# R181C.net
KiCad netlist of a schematic drawn in EAGLE
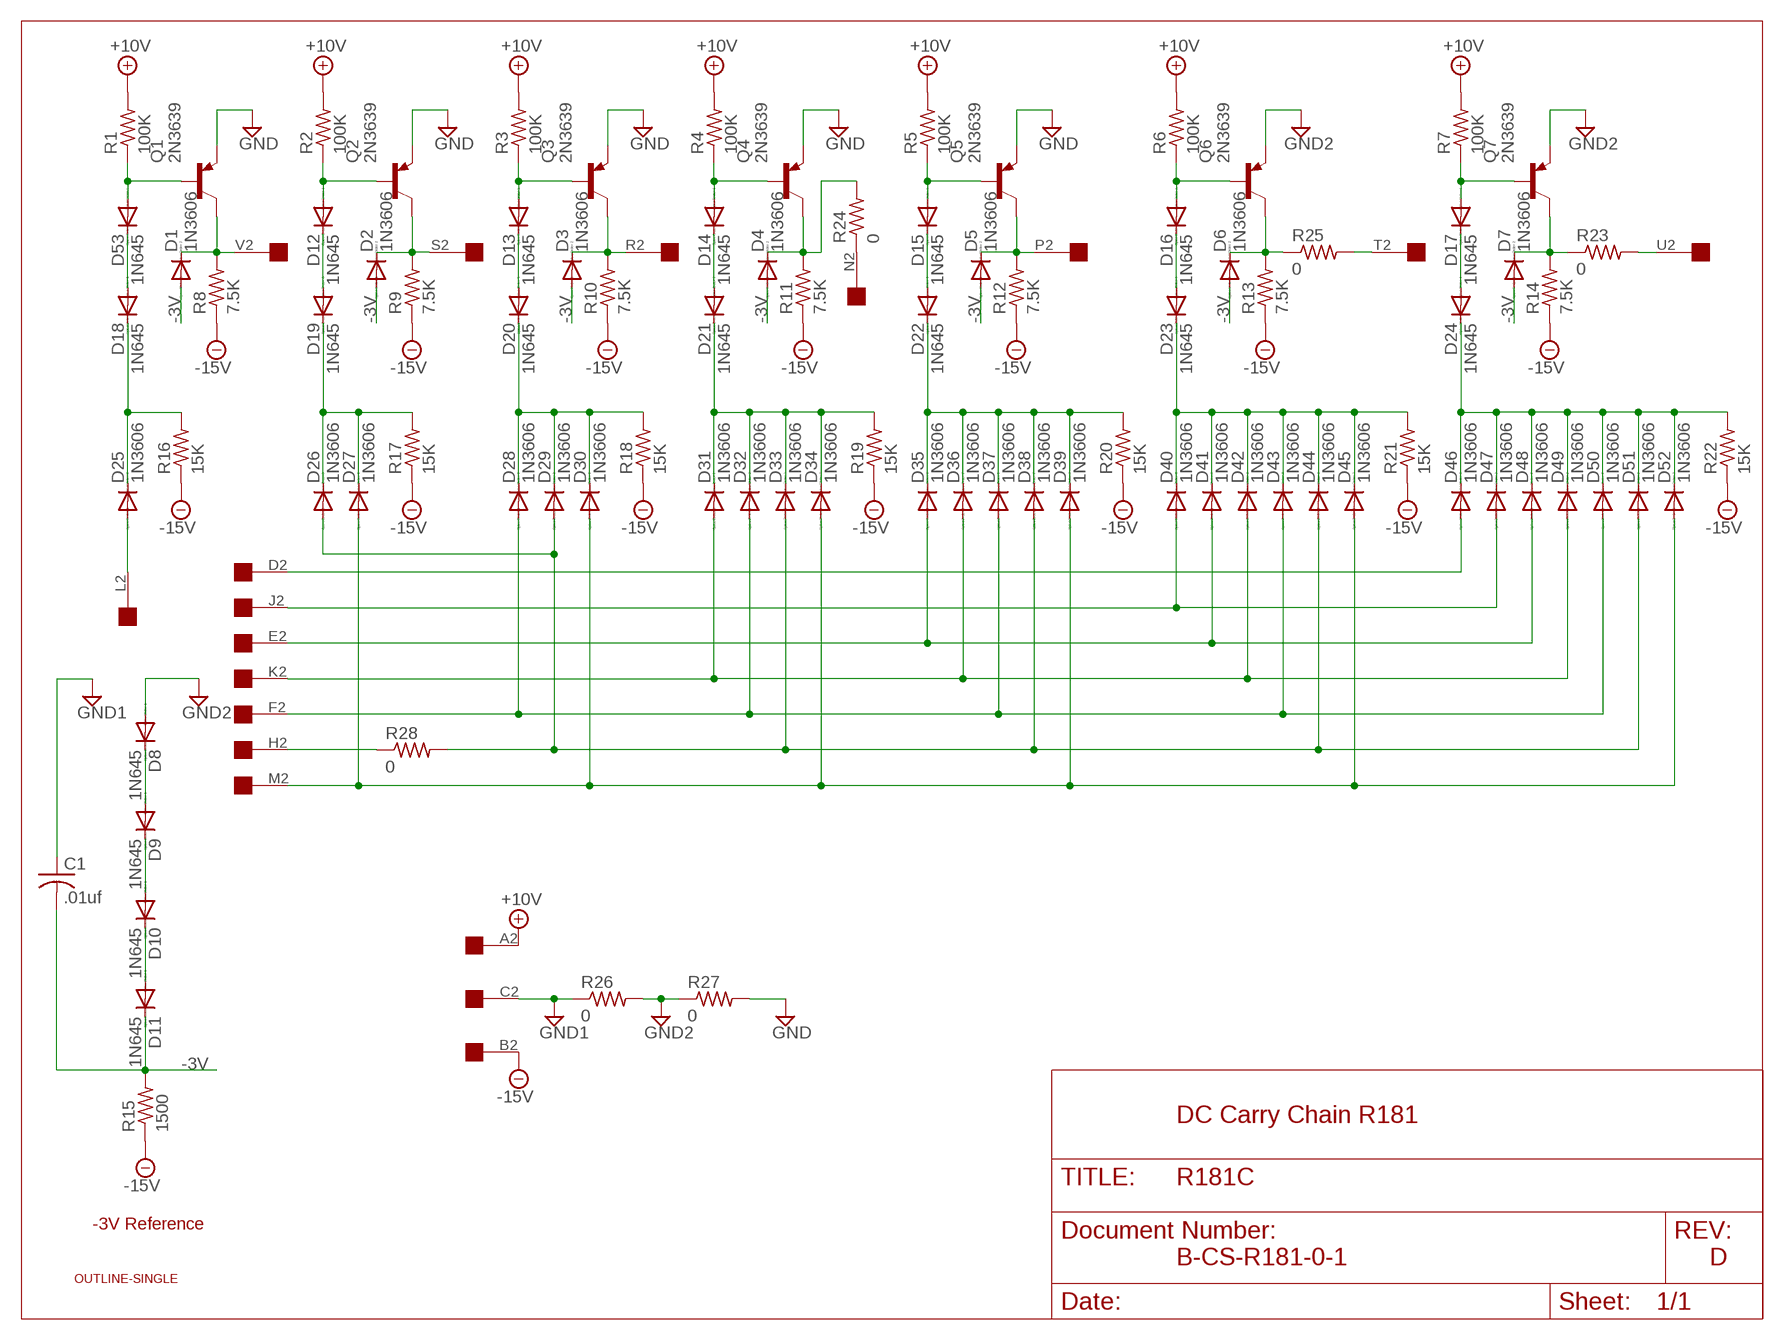
[diagram p0: schematic, sheet 1]

(export (version "E")
  (design (tool "Eeschema 10.0.6"))
  (components
    (comp (ref "C1")
      (value ".01uf")
      (footprint "eagle-import:C050-025X075")
      (libsource (lib "eagle-import") (part "C-US050-025X075"))
    )
    (comp (ref "D1")
      (value "1N3606")
      (footprint "eagle-import:DO35-10")
      (libsource (lib "eagle-import") (part "1N4148DO35-10"))
    )
    (comp (ref "D2")
      (value "1N3606")
      (footprint "eagle-import:DO35-10")
      (libsource (lib "eagle-import") (part "1N4148DO35-10"))
    )
    (comp (ref "D3")
      (value "1N3606")
      (footprint "eagle-import:DO35-10")
      (libsource (lib "eagle-import") (part "1N4148DO35-10"))
    )
    (comp (ref "D4")
      (value "1N3606")
      (footprint "eagle-import:DO35-10")
      (libsource (lib "eagle-import") (part "1N4148DO35-10"))
    )
    (comp (ref "D5")
      (value "1N3606")
      (footprint "eagle-import:DO35-10")
      (libsource (lib "eagle-import") (part "1N4148DO35-10"))
    )
    (comp (ref "D6")
      (value "1N3606")
      (footprint "eagle-import:DO35-10")
      (libsource (lib "eagle-import") (part "1N4148DO35-10"))
    )
    (comp (ref "D7")
      (value "1N3606")
      (footprint "eagle-import:DO35-10")
      (libsource (lib "eagle-import") (part "1N4148DO35-10"))
    )
    (comp (ref "D8")
      (value "1N645")
      (footprint "eagle-import:DO35-10")
      (libsource (lib "eagle-import") (part "1N4148DO35-10"))
    )
    (comp (ref "D9")
      (value "1N645")
      (footprint "eagle-import:DO35-10")
      (libsource (lib "eagle-import") (part "1N4148DO35-10"))
    )
    (comp (ref "D10")
      (value "1N645")
      (footprint "eagle-import:DO35-10")
      (libsource (lib "eagle-import") (part "1N4148DO35-10"))
    )
    (comp (ref "D11")
      (value "1N645")
      (footprint "eagle-import:DO35-10")
      (libsource (lib "eagle-import") (part "1N4148DO35-10"))
    )
    (comp (ref "D12")
      (value "1N645")
      (footprint "eagle-import:DO35-10")
      (libsource (lib "eagle-import") (part "1N4148DO35-10"))
    )
    (comp (ref "D13")
      (value "1N645")
      (footprint "eagle-import:DO35-10")
      (libsource (lib "eagle-import") (part "1N4148DO35-10"))
    )
    (comp (ref "D14")
      (value "1N645")
      (footprint "eagle-import:DO35-10")
      (libsource (lib "eagle-import") (part "1N4148DO35-10"))
    )
    (comp (ref "D15")
      (value "1N645")
      (footprint "eagle-import:DO35-10")
      (libsource (lib "eagle-import") (part "1N4148DO35-10"))
    )
    (comp (ref "D16")
      (value "1N645")
      (footprint "eagle-import:DO35-10")
      (libsource (lib "eagle-import") (part "1N4148DO35-10"))
    )
    (comp (ref "D17")
      (value "1N645")
      (footprint "eagle-import:DO35-10")
      (libsource (lib "eagle-import") (part "1N4148DO35-10"))
    )
    (comp (ref "D18")
      (value "1N645")
      (footprint "eagle-import:DO35-10")
      (libsource (lib "eagle-import") (part "1N4148DO35-10"))
    )
    (comp (ref "D19")
      (value "1N645")
      (footprint "eagle-import:DO35-10")
      (libsource (lib "eagle-import") (part "1N4148DO35-10"))
    )
    (comp (ref "D20")
      (value "1N645")
      (footprint "eagle-import:DO35-10")
      (libsource (lib "eagle-import") (part "1N4148DO35-10"))
    )
    (comp (ref "D21")
      (value "1N645")
      (footprint "eagle-import:DO35-10")
      (libsource (lib "eagle-import") (part "1N4148DO35-10"))
    )
    (comp (ref "D22")
      (value "1N645")
      (footprint "eagle-import:DO35-10")
      (libsource (lib "eagle-import") (part "1N4148DO35-10"))
    )
    (comp (ref "D23")
      (value "1N645")
      (footprint "eagle-import:DO35-10")
      (libsource (lib "eagle-import") (part "1N4148DO35-10"))
    )
    (comp (ref "D24")
      (value "1N645")
      (footprint "eagle-import:DO35-10")
      (libsource (lib "eagle-import") (part "1N4148DO35-10"))
    )
    (comp (ref "D25")
      (value "1N3606")
      (footprint "eagle-import:DO35-10")
      (libsource (lib "eagle-import") (part "1N4148DO35-10"))
    )
    (comp (ref "D26")
      (value "1N3606")
      (footprint "eagle-import:DO35-10")
      (libsource (lib "eagle-import") (part "1N4148DO35-10"))
    )
    (comp (ref "D27")
      (value "1N3606")
      (footprint "eagle-import:DO35-10")
      (libsource (lib "eagle-import") (part "1N4148DO35-10"))
    )
    (comp (ref "D28")
      (value "1N3606")
      (footprint "eagle-import:DO35-10")
      (libsource (lib "eagle-import") (part "1N4148DO35-10"))
    )
    (comp (ref "D29")
      (value "1N3606")
      (footprint "eagle-import:DO35-10")
      (libsource (lib "eagle-import") (part "1N4148DO35-10"))
    )
    (comp (ref "D30")
      (value "1N3606")
      (footprint "eagle-import:DO35-10")
      (libsource (lib "eagle-import") (part "1N4148DO35-10"))
    )
    (comp (ref "D31")
      (value "1N3606")
      (footprint "eagle-import:DO35-10")
      (libsource (lib "eagle-import") (part "1N4148DO35-10"))
    )
    (comp (ref "D32")
      (value "1N3606")
      (footprint "eagle-import:DO35-10")
      (libsource (lib "eagle-import") (part "1N4148DO35-10"))
    )
    (comp (ref "D33")
      (value "1N3606")
      (footprint "eagle-import:DO35-10")
      (libsource (lib "eagle-import") (part "1N4148DO35-10"))
    )
    (comp (ref "D34")
      (value "1N3606")
      (footprint "eagle-import:DO35-10")
      (libsource (lib "eagle-import") (part "1N4148DO35-10"))
    )
    (comp (ref "D35")
      (value "1N3606")
      (footprint "eagle-import:DO35-10")
      (libsource (lib "eagle-import") (part "1N4148DO35-10"))
    )
    (comp (ref "D36")
      (value "1N3606")
      (footprint "eagle-import:DO35-10")
      (libsource (lib "eagle-import") (part "1N4148DO35-10"))
    )
    (comp (ref "D37")
      (value "1N3606")
      (footprint "eagle-import:DO35-10")
      (libsource (lib "eagle-import") (part "1N4148DO35-10"))
    )
    (comp (ref "D38")
      (value "1N3606")
      (footprint "eagle-import:DO35-10")
      (libsource (lib "eagle-import") (part "1N4148DO35-10"))
    )
    (comp (ref "D39")
      (value "1N3606")
      (footprint "eagle-import:DO35-10")
      (libsource (lib "eagle-import") (part "1N4148DO35-10"))
    )
    (comp (ref "D40")
      (value "1N3606")
      (footprint "eagle-import:DO35-10")
      (libsource (lib "eagle-import") (part "1N4148DO35-10"))
    )
    (comp (ref "D41")
      (value "1N3606")
      (footprint "eagle-import:DO35-10")
      (libsource (lib "eagle-import") (part "1N4148DO35-10"))
    )
    (comp (ref "D42")
      (value "1N3606")
      (footprint "eagle-import:DO35-10")
      (libsource (lib "eagle-import") (part "1N4148DO35-10"))
    )
    (comp (ref "D43")
      (value "1N3606")
      (footprint "eagle-import:DO35-10")
      (libsource (lib "eagle-import") (part "1N4148DO35-10"))
    )
    (comp (ref "D44")
      (value "1N3606")
      (footprint "eagle-import:DO35-10")
      (libsource (lib "eagle-import") (part "1N4148DO35-10"))
    )
    (comp (ref "D45")
      (value "1N3606")
      (footprint "eagle-import:DO35-10")
      (libsource (lib "eagle-import") (part "1N4148DO35-10"))
    )
    (comp (ref "D46")
      (value "1N3606")
      (footprint "eagle-import:DO35-10")
      (libsource (lib "eagle-import") (part "1N4148DO35-10"))
    )
    (comp (ref "D47")
      (value "1N3606")
      (footprint "eagle-import:DO35-10")
      (libsource (lib "eagle-import") (part "1N4148DO35-10"))
    )
    (comp (ref "D48")
      (value "1N3606")
      (footprint "eagle-import:DO35-10")
      (libsource (lib "eagle-import") (part "1N4148DO35-10"))
    )
    (comp (ref "D49")
      (value "1N3606")
      (footprint "eagle-import:DO35-10")
      (libsource (lib "eagle-import") (part "1N4148DO35-10"))
    )
    (comp (ref "D50")
      (value "1N3606")
      (footprint "eagle-import:DO35-10")
      (libsource (lib "eagle-import") (part "1N4148DO35-10"))
    )
    (comp (ref "D51")
      (value "1N3606")
      (footprint "eagle-import:DO35-10")
      (libsource (lib "eagle-import") (part "1N4148DO35-10"))
    )
    (comp (ref "D52")
      (value "1N3606")
      (footprint "eagle-import:DO35-10")
      (libsource (lib "eagle-import") (part "1N4148DO35-10"))
    )
    (comp (ref "D53")
      (value "1N645")
      (footprint "eagle-import:DO35-10")
      (libsource (lib "eagle-import") (part "1N4148DO35-10"))
    )
    (comp (ref "Q1")
      (value "2N3639")
      (footprint "eagle-import:TO39")
      (libsource (lib "eagle-import") (part "2N3637"))
    )
    (comp (ref "Q2")
      (value "2N3639")
      (footprint "eagle-import:TO39")
      (libsource (lib "eagle-import") (part "2N3637"))
    )
    (comp (ref "Q3")
      (value "2N3639")
      (footprint "eagle-import:TO39")
      (libsource (lib "eagle-import") (part "2N3637"))
    )
    (comp (ref "Q4")
      (value "2N3639")
      (footprint "eagle-import:TO39")
      (libsource (lib "eagle-import") (part "2N3637"))
    )
    (comp (ref "Q5")
      (value "2N3639")
      (footprint "eagle-import:TO39")
      (libsource (lib "eagle-import") (part "2N3637"))
    )
    (comp (ref "Q6")
      (value "2N3639")
      (footprint "eagle-import:TO39")
      (libsource (lib "eagle-import") (part "2N3637"))
    )
    (comp (ref "Q7")
      (value "2N3639")
      (footprint "eagle-import:TO39")
      (libsource (lib "eagle-import") (part "2N3637"))
    )
    (comp (ref "R1")
      (value "100K")
      (footprint "eagle-import:0207_10")
      (libsource (lib "eagle-import") (part "R-US_0207/10"))
    )
    (comp (ref "R2")
      (value "100K")
      (footprint "eagle-import:0207_10")
      (libsource (lib "eagle-import") (part "R-US_0207/10"))
    )
    (comp (ref "R3")
      (value "100K")
      (footprint "eagle-import:0207_10")
      (libsource (lib "eagle-import") (part "R-US_0207/10"))
    )
    (comp (ref "R4")
      (value "100K")
      (footprint "eagle-import:0207_10")
      (libsource (lib "eagle-import") (part "R-US_0207/10"))
    )
    (comp (ref "R5")
      (value "100K")
      (footprint "eagle-import:0207_10")
      (libsource (lib "eagle-import") (part "R-US_0207/10"))
    )
    (comp (ref "R6")
      (value "100K")
      (footprint "eagle-import:0207_10")
      (libsource (lib "eagle-import") (part "R-US_0207/10"))
    )
    (comp (ref "R7")
      (value "100K")
      (footprint "eagle-import:0207_10")
      (libsource (lib "eagle-import") (part "R-US_0207/10"))
    )
    (comp (ref "R8")
      (value "7.5K")
      (footprint "eagle-import:0207_10")
      (libsource (lib "eagle-import") (part "R-US_0207/10"))
    )
    (comp (ref "R9")
      (value "7.5K")
      (footprint "eagle-import:0207_10")
      (libsource (lib "eagle-import") (part "R-US_0207/10"))
    )
    (comp (ref "R10")
      (value "7.5K")
      (footprint "eagle-import:0207_10")
      (libsource (lib "eagle-import") (part "R-US_0207/10"))
    )
    (comp (ref "R11")
      (value "7.5K")
      (footprint "eagle-import:0207_10")
      (libsource (lib "eagle-import") (part "R-US_0207/10"))
    )
    (comp (ref "R12")
      (value "7.5K")
      (footprint "eagle-import:0207_10")
      (libsource (lib "eagle-import") (part "R-US_0207/10"))
    )
    (comp (ref "R13")
      (value "7.5K")
      (footprint "eagle-import:0207_10")
      (libsource (lib "eagle-import") (part "R-US_0207/10"))
    )
    (comp (ref "R14")
      (value "7.5K")
      (footprint "eagle-import:0207_10")
      (libsource (lib "eagle-import") (part "R-US_0207/10"))
    )
    (comp (ref "R15")
      (value "1500")
      (footprint "eagle-import:0207_10")
      (libsource (lib "eagle-import") (part "R-US_0207/10"))
    )
    (comp (ref "R16")
      (value "15K")
      (footprint "eagle-import:0207_10")
      (libsource (lib "eagle-import") (part "R-US_0207/10"))
    )
    (comp (ref "R17")
      (value "15K")
      (footprint "eagle-import:0207_10")
      (libsource (lib "eagle-import") (part "R-US_0207/10"))
    )
    (comp (ref "R18")
      (value "15K")
      (footprint "eagle-import:0207_10")
      (libsource (lib "eagle-import") (part "R-US_0207/10"))
    )
    (comp (ref "R19")
      (value "15K")
      (footprint "eagle-import:0207_10")
      (libsource (lib "eagle-import") (part "R-US_0207/10"))
    )
    (comp (ref "R20")
      (value "15K")
      (footprint "eagle-import:0207_10")
      (libsource (lib "eagle-import") (part "R-US_0207/10"))
    )
    (comp (ref "R21")
      (value "15K")
      (footprint "eagle-import:0207_10")
      (libsource (lib "eagle-import") (part "R-US_0207/10"))
    )
    (comp (ref "R22")
      (value "15K")
      (footprint "eagle-import:0207_10")
      (libsource (lib "eagle-import") (part "R-US_0207/10"))
    )
    (comp (ref "R23")
      (value "0")
      (footprint "eagle-import:0207_10")
      (libsource (lib "eagle-import") (part "R-US_0207/10"))
    )
    (comp (ref "R24")
      (value "0")
      (footprint "eagle-import:0207_10")
      (libsource (lib "eagle-import") (part "R-US_0207/10"))
    )
    (comp (ref "R25")
      (value "0")
      (footprint "eagle-import:0207_10")
      (libsource (lib "eagle-import") (part "R-US_0207/10"))
    )
    (comp (ref "R26")
      (value "0")
      (footprint "eagle-import:0207_10")
      (libsource (lib "eagle-import") (part "R-US_0207/10"))
    )
    (comp (ref "R27")
      (value "0")
      (footprint "eagle-import:0207_10")
      (libsource (lib "eagle-import") (part "R-US_0207/10"))
    )
    (comp (ref "R28")
      (value "0")
      (footprint "eagle-import:0207_10")
      (libsource (lib "eagle-import") (part "R-US_0207/10"))
    )
    (comp (ref "U$1")
      (value "OUTLINE-SINGLE")
      (footprint "eagle-import:SINGLE")
      (libsource (lib "eagle-import") (part "OUTLINE-SINGLE"))
    )
    (comp (ref "U$2")
      (value "EDGE-1")
      (footprint "eagle-import:EDGE-CON1")
      (libsource (lib "eagle-import") (part "EDGE-1"))
    )
  )
  (nets
    (net (code "1") (name "+10V") (class "Default")
      (node (ref "R1") (pin "2") (pinfunction "2_2") (pintype "passive"))
      (node (ref "R2") (pin "2") (pinfunction "2_2") (pintype "passive"))
      (node (ref "R3") (pin "2") (pinfunction "2_2") (pintype "passive"))
      (node (ref "R4") (pin "2") (pinfunction "2_2") (pintype "passive"))
      (node (ref "R5") (pin "2") (pinfunction "2_2") (pintype "passive"))
      (node (ref "R6") (pin "2") (pinfunction "2_2") (pintype "passive"))
      (node (ref "R7") (pin "2") (pinfunction "2_2") (pintype "passive"))
      (node (ref "U$2") (pin "A2") (pinfunction "1_A2") (pintype "bidirectional"))
    )
    (net (code "2") (name "-15V") (class "Default")
      (node (ref "R10") (pin "1") (pinfunction "1_1") (pintype "passive"))
      (node (ref "R11") (pin "1") (pinfunction "1_1") (pintype "passive"))
      (node (ref "R12") (pin "1") (pinfunction "1_1") (pintype "passive"))
      (node (ref "R13") (pin "1") (pinfunction "1_1") (pintype "passive"))
      (node (ref "R14") (pin "1") (pinfunction "1_1") (pintype "passive"))
      (node (ref "R15") (pin "1") (pinfunction "1_1") (pintype "passive"))
      (node (ref "R16") (pin "1") (pinfunction "1_1") (pintype "passive"))
      (node (ref "R17") (pin "1") (pinfunction "1_1") (pintype "passive"))
      (node (ref "R18") (pin "1") (pinfunction "1_1") (pintype "passive"))
      (node (ref "R19") (pin "1") (pinfunction "1_1") (pintype "passive"))
      (node (ref "R20") (pin "1") (pinfunction "1_1") (pintype "passive"))
      (node (ref "R21") (pin "1") (pinfunction "1_1") (pintype "passive"))
      (node (ref "R22") (pin "1") (pinfunction "1_1") (pintype "passive"))
      (node (ref "R8") (pin "1") (pinfunction "1_1") (pintype "passive"))
      (node (ref "R9") (pin "1") (pinfunction "1_1") (pintype "passive"))
      (node (ref "U$2") (pin "B2") (pinfunction "1_B2") (pintype "bidirectional"))
    )
    (net (code "3") (name "/-3V") (class "Default")
      (node (ref "C1") (pin "2") (pinfunction "2_2") (pintype "passive"))
      (node (ref "D1") (pin "A") (pinfunction "A_A") (pintype "passive"))
      (node (ref "D11") (pin "C") (pinfunction "C_C") (pintype "passive"))
      (node (ref "D2") (pin "A") (pinfunction "A_A") (pintype "passive"))
      (node (ref "D3") (pin "A") (pinfunction "A_A") (pintype "passive"))
      (node (ref "D4") (pin "A") (pinfunction "A_A") (pintype "passive"))
      (node (ref "D5") (pin "A") (pinfunction "A_A") (pintype "passive"))
      (node (ref "D6") (pin "A") (pinfunction "A_A") (pintype "passive"))
      (node (ref "D7") (pin "A") (pinfunction "A_A") (pintype "passive"))
      (node (ref "R15") (pin "2") (pinfunction "2_2") (pintype "passive"))
    )
    (net (code "4") (name "GND") (class "Default")
      (node (ref "Q1") (pin "1") (pinfunction "E_1") (pintype "passive"))
      (node (ref "Q2") (pin "1") (pinfunction "E_1") (pintype "passive"))
      (node (ref "Q3") (pin "1") (pinfunction "E_1") (pintype "passive"))
      (node (ref "Q4") (pin "1") (pinfunction "E_1") (pintype "passive"))
      (node (ref "Q5") (pin "1") (pinfunction "E_1") (pintype "passive"))
      (node (ref "R27") (pin "2") (pinfunction "2_2") (pintype "passive"))
    )
    (net (code "5") (name "GND1") (class "Default")
      (node (ref "C1") (pin "1") (pinfunction "1_1") (pintype "passive"))
      (node (ref "R26") (pin "1") (pinfunction "1_1") (pintype "passive"))
      (node (ref "U$2") (pin "C2") (pinfunction "1_C2") (pintype "bidirectional"))
    )
    (net (code "6") (name "GND2") (class "Default")
      (node (ref "D8") (pin "A") (pinfunction "A_A") (pintype "passive"))
      (node (ref "Q6") (pin "1") (pinfunction "E_1") (pintype "passive"))
      (node (ref "Q7") (pin "1") (pinfunction "E_1") (pintype "passive"))
      (node (ref "R26") (pin "2") (pinfunction "2_2") (pintype "passive"))
      (node (ref "R27") (pin "1") (pinfunction "1_1") (pintype "passive"))
    )
    (net (code "7") (name "Net-(D8-PadC)") (class "Default")
      (node (ref "D8") (pin "C") (pinfunction "C_C") (pintype "passive"))
      (node (ref "D9") (pin "A") (pinfunction "A_A") (pintype "passive"))
    )
    (net (code "8") (name "Net-(D10-PadA)") (class "Default")
      (node (ref "D10") (pin "A") (pinfunction "A_A") (pintype "passive"))
      (node (ref "D9") (pin "C") (pinfunction "C_C") (pintype "passive"))
    )
    (net (code "9") (name "Net-(D10-PadC)") (class "Default")
      (node (ref "D10") (pin "C") (pinfunction "C_C") (pintype "passive"))
      (node (ref "D11") (pin "A") (pinfunction "A_A") (pintype "passive"))
    )
    (net (code "10") (name "Net-(D12-PadC)") (class "Default")
      (node (ref "D12") (pin "C") (pinfunction "C_C") (pintype "passive"))
      (node (ref "D19") (pin "A") (pinfunction "A_A") (pintype "passive"))
    )
    (net (code "11") (name "Net-(D13-PadC)") (class "Default")
      (node (ref "D13") (pin "C") (pinfunction "C_C") (pintype "passive"))
      (node (ref "D20") (pin "A") (pinfunction "A_A") (pintype "passive"))
    )
    (net (code "12") (name "Net-(D14-PadC)") (class "Default")
      (node (ref "D14") (pin "C") (pinfunction "C_C") (pintype "passive"))
      (node (ref "D21") (pin "A") (pinfunction "A_A") (pintype "passive"))
    )
    (net (code "13") (name "Net-(D15-PadC)") (class "Default")
      (node (ref "D15") (pin "C") (pinfunction "C_C") (pintype "passive"))
      (node (ref "D22") (pin "A") (pinfunction "A_A") (pintype "passive"))
    )
    (net (code "14") (name "Net-(D16-PadC)") (class "Default")
      (node (ref "D16") (pin "C") (pinfunction "C_C") (pintype "passive"))
      (node (ref "D23") (pin "A") (pinfunction "A_A") (pintype "passive"))
    )
    (net (code "15") (name "Net-(D17-PadC)") (class "Default")
      (node (ref "D17") (pin "C") (pinfunction "C_C") (pintype "passive"))
      (node (ref "D24") (pin "A") (pinfunction "A_A") (pintype "passive"))
    )
    (net (code "16") (name "Net-(D18-PadA)") (class "Default")
      (node (ref "D18") (pin "A") (pinfunction "A_A") (pintype "passive"))
      (node (ref "D53") (pin "C") (pinfunction "C_C") (pintype "passive"))
    )
    (net (code "17") (name "Net-(D18-PadC)") (class "Default")
      (node (ref "D18") (pin "C") (pinfunction "C_C") (pintype "passive"))
      (node (ref "D25") (pin "C") (pinfunction "C_C") (pintype "passive"))
      (node (ref "R16") (pin "2") (pinfunction "2_2") (pintype "passive"))
    )
    (net (code "18") (name "Net-(D19-PadC)") (class "Default")
      (node (ref "D19") (pin "C") (pinfunction "C_C") (pintype "passive"))
      (node (ref "D26") (pin "C") (pinfunction "C_C") (pintype "passive"))
      (node (ref "D27") (pin "C") (pinfunction "C_C") (pintype "passive"))
      (node (ref "R17") (pin "2") (pinfunction "2_2") (pintype "passive"))
    )
    (net (code "19") (name "Net-(D20-PadC)") (class "Default")
      (node (ref "D20") (pin "C") (pinfunction "C_C") (pintype "passive"))
      (node (ref "D28") (pin "C") (pinfunction "C_C") (pintype "passive"))
      (node (ref "D29") (pin "C") (pinfunction "C_C") (pintype "passive"))
      (node (ref "D30") (pin "C") (pinfunction "C_C") (pintype "passive"))
      (node (ref "R18") (pin "2") (pinfunction "2_2") (pintype "passive"))
    )
    (net (code "20") (name "Net-(D21-PadC)") (class "Default")
      (node (ref "D21") (pin "C") (pinfunction "C_C") (pintype "passive"))
      (node (ref "D31") (pin "C") (pinfunction "C_C") (pintype "passive"))
      (node (ref "D32") (pin "C") (pinfunction "C_C") (pintype "passive"))
      (node (ref "D33") (pin "C") (pinfunction "C_C") (pintype "passive"))
      (node (ref "D34") (pin "C") (pinfunction "C_C") (pintype "passive"))
      (node (ref "R19") (pin "2") (pinfunction "2_2") (pintype "passive"))
    )
    (net (code "21") (name "Net-(D22-PadC)") (class "Default")
      (node (ref "D22") (pin "C") (pinfunction "C_C") (pintype "passive"))
      (node (ref "D35") (pin "C") (pinfunction "C_C") (pintype "passive"))
      (node (ref "D36") (pin "C") (pinfunction "C_C") (pintype "passive"))
      (node (ref "D37") (pin "C") (pinfunction "C_C") (pintype "passive"))
      (node (ref "D38") (pin "C") (pinfunction "C_C") (pintype "passive"))
      (node (ref "D39") (pin "C") (pinfunction "C_C") (pintype "passive"))
      (node (ref "R20") (pin "2") (pinfunction "2_2") (pintype "passive"))
    )
    (net (code "22") (name "Net-(D23-PadC)") (class "Default")
      (node (ref "D23") (pin "C") (pinfunction "C_C") (pintype "passive"))
      (node (ref "D40") (pin "C") (pinfunction "C_C") (pintype "passive"))
      (node (ref "D41") (pin "C") (pinfunction "C_C") (pintype "passive"))
      (node (ref "D42") (pin "C") (pinfunction "C_C") (pintype "passive"))
      (node (ref "D43") (pin "C") (pinfunction "C_C") (pintype "passive"))
      (node (ref "D44") (pin "C") (pinfunction "C_C") (pintype "passive"))
      (node (ref "D45") (pin "C") (pinfunction "C_C") (pintype "passive"))
      (node (ref "R21") (pin "2") (pinfunction "2_2") (pintype "passive"))
    )
    (net (code "23") (name "Net-(D24-PadC)") (class "Default")
      (node (ref "D24") (pin "C") (pinfunction "C_C") (pintype "passive"))
      (node (ref "D46") (pin "C") (pinfunction "C_C") (pintype "passive"))
      (node (ref "D47") (pin "C") (pinfunction "C_C") (pintype "passive"))
      (node (ref "D48") (pin "C") (pinfunction "C_C") (pintype "passive"))
      (node (ref "D49") (pin "C") (pinfunction "C_C") (pintype "passive"))
      (node (ref "D50") (pin "C") (pinfunction "C_C") (pintype "passive"))
      (node (ref "D51") (pin "C") (pinfunction "C_C") (pintype "passive"))
      (node (ref "D52") (pin "C") (pinfunction "C_C") (pintype "passive"))
      (node (ref "R22") (pin "2") (pinfunction "2_2") (pintype "passive"))
    )
    (net (code "24") (name "Net-(D26-PadA)") (class "Default")
      (node (ref "D26") (pin "A") (pinfunction "A_A") (pintype "passive"))
      (node (ref "D29") (pin "A") (pinfunction "A_A") (pintype "passive"))
      (node (ref "D33") (pin "A") (pinfunction "A_A") (pintype "passive"))
      (node (ref "D38") (pin "A") (pinfunction "A_A") (pintype "passive"))
      (node (ref "D44") (pin "A") (pinfunction "A_A") (pintype "passive"))
      (node (ref "D51") (pin "A") (pinfunction "A_A") (pintype "passive"))
      (node (ref "R28") (pin "2") (pinfunction "2_2") (pintype "passive"))
    )
    (net (code "25") (name "Net-(Q1-B)") (class "Default")
      (node (ref "D53") (pin "A") (pinfunction "A_A") (pintype "passive"))
      (node (ref "Q1") (pin "2") (pinfunction "B_2") (pintype "passive"))
      (node (ref "R1") (pin "1") (pinfunction "1_1") (pintype "passive"))
    )
    (net (code "26") (name "Net-(Q1-C)") (class "Default")
      (node (ref "D1") (pin "C") (pinfunction "C_C") (pintype "passive"))
      (node (ref "Q1") (pin "3") (pinfunction "C_3") (pintype "passive"))
      (node (ref "R8") (pin "2") (pinfunction "2_2") (pintype "passive"))
      (node (ref "U$2") (pin "V2") (pinfunction "1_V2") (pintype "bidirectional"))
    )
    (net (code "27") (name "Net-(Q2-B)") (class "Default")
      (node (ref "D12") (pin "A") (pinfunction "A_A") (pintype "passive"))
      (node (ref "Q2") (pin "2") (pinfunction "B_2") (pintype "passive"))
      (node (ref "R2") (pin "1") (pinfunction "1_1") (pintype "passive"))
    )
    (net (code "28") (name "Net-(Q2-C)") (class "Default")
      (node (ref "D2") (pin "C") (pinfunction "C_C") (pintype "passive"))
      (node (ref "Q2") (pin "3") (pinfunction "C_3") (pintype "passive"))
      (node (ref "R9") (pin "2") (pinfunction "2_2") (pintype "passive"))
      (node (ref "U$2") (pin "S2") (pinfunction "1_S2") (pintype "bidirectional"))
    )
    (net (code "29") (name "Net-(Q3-B)") (class "Default")
      (node (ref "D13") (pin "A") (pinfunction "A_A") (pintype "passive"))
      (node (ref "Q3") (pin "2") (pinfunction "B_2") (pintype "passive"))
      (node (ref "R3") (pin "1") (pinfunction "1_1") (pintype "passive"))
    )
    (net (code "30") (name "Net-(Q3-C)") (class "Default")
      (node (ref "D3") (pin "C") (pinfunction "C_C") (pintype "passive"))
      (node (ref "Q3") (pin "3") (pinfunction "C_3") (pintype "passive"))
      (node (ref "R10") (pin "2") (pinfunction "2_2") (pintype "passive"))
      (node (ref "U$2") (pin "R2") (pinfunction "1_R2") (pintype "bidirectional"))
    )
    (net (code "31") (name "Net-(Q4-B)") (class "Default")
      (node (ref "D14") (pin "A") (pinfunction "A_A") (pintype "passive"))
      (node (ref "Q4") (pin "2") (pinfunction "B_2") (pintype "passive"))
      (node (ref "R4") (pin "1") (pinfunction "1_1") (pintype "passive"))
    )
    (net (code "32") (name "Net-(Q4-C)") (class "Default")
      (node (ref "D4") (pin "C") (pinfunction "C_C") (pintype "passive"))
      (node (ref "Q4") (pin "3") (pinfunction "C_3") (pintype "passive"))
      (node (ref "R11") (pin "2") (pinfunction "2_2") (pintype "passive"))
      (node (ref "R24") (pin "2") (pinfunction "2_2") (pintype "passive"))
    )
    (net (code "33") (name "Net-(Q5-B)") (class "Default")
      (node (ref "D15") (pin "A") (pinfunction "A_A") (pintype "passive"))
      (node (ref "Q5") (pin "2") (pinfunction "B_2") (pintype "passive"))
      (node (ref "R5") (pin "1") (pinfunction "1_1") (pintype "passive"))
    )
    (net (code "34") (name "Net-(Q5-C)") (class "Default")
      (node (ref "D5") (pin "C") (pinfunction "C_C") (pintype "passive"))
      (node (ref "Q5") (pin "3") (pinfunction "C_3") (pintype "passive"))
      (node (ref "R12") (pin "2") (pinfunction "2_2") (pintype "passive"))
      (node (ref "U$2") (pin "P2") (pinfunction "1_P2") (pintype "bidirectional"))
    )
    (net (code "35") (name "Net-(Q6-B)") (class "Default")
      (node (ref "D16") (pin "A") (pinfunction "A_A") (pintype "passive"))
      (node (ref "Q6") (pin "2") (pinfunction "B_2") (pintype "passive"))
      (node (ref "R6") (pin "1") (pinfunction "1_1") (pintype "passive"))
    )
    (net (code "36") (name "Net-(Q6-C)") (class "Default")
      (node (ref "D6") (pin "C") (pinfunction "C_C") (pintype "passive"))
      (node (ref "Q6") (pin "3") (pinfunction "C_3") (pintype "passive"))
      (node (ref "R13") (pin "2") (pinfunction "2_2") (pintype "passive"))
      (node (ref "R25") (pin "1") (pinfunction "1_1") (pintype "passive"))
    )
    (net (code "37") (name "Net-(Q7-B)") (class "Default")
      (node (ref "D17") (pin "A") (pinfunction "A_A") (pintype "passive"))
      (node (ref "Q7") (pin "2") (pinfunction "B_2") (pintype "passive"))
      (node (ref "R7") (pin "1") (pinfunction "1_1") (pintype "passive"))
    )
    (net (code "38") (name "Net-(Q7-C)") (class "Default")
      (node (ref "D7") (pin "C") (pinfunction "C_C") (pintype "passive"))
      (node (ref "Q7") (pin "3") (pinfunction "C_3") (pintype "passive"))
      (node (ref "R14") (pin "2") (pinfunction "2_2") (pintype "passive"))
      (node (ref "R23") (pin "1") (pinfunction "1_1") (pintype "passive"))
    )
    (net (code "39") (name "Net-(U$2D-1)") (class "Default")
      (node (ref "D46") (pin "A") (pinfunction "A_A") (pintype "passive"))
      (node (ref "U$2") (pin "D2") (pinfunction "1_D2") (pintype "bidirectional"))
    )
    (net (code "40") (name "Net-(U$2E-1)") (class "Default")
      (node (ref "D35") (pin "A") (pinfunction "A_A") (pintype "passive"))
      (node (ref "D41") (pin "A") (pinfunction "A_A") (pintype "passive"))
      (node (ref "D48") (pin "A") (pinfunction "A_A") (pintype "passive"))
      (node (ref "U$2") (pin "E2") (pinfunction "1_E2") (pintype "bidirectional"))
    )
    (net (code "41") (name "Net-(U$2F-1)") (class "Default")
      (node (ref "D28") (pin "A") (pinfunction "A_A") (pintype "passive"))
      (node (ref "D32") (pin "A") (pinfunction "A_A") (pintype "passive"))
      (node (ref "D37") (pin "A") (pinfunction "A_A") (pintype "passive"))
      (node (ref "D43") (pin "A") (pinfunction "A_A") (pintype "passive"))
      (node (ref "D50") (pin "A") (pinfunction "A_A") (pintype "passive"))
      (node (ref "U$2") (pin "F2") (pinfunction "1_F2") (pintype "bidirectional"))
    )
    (net (code "42") (name "Net-(U$2G-1)") (class "Default")
      (node (ref "R28") (pin "1") (pinfunction "1_1") (pintype "passive"))
      (node (ref "U$2") (pin "H2") (pinfunction "1_H2") (pintype "bidirectional"))
    )
    (net (code "43") (name "Net-(U$2H-1)") (class "Default")
      (node (ref "D40") (pin "A") (pinfunction "A_A") (pintype "passive"))
      (node (ref "D47") (pin "A") (pinfunction "A_A") (pintype "passive"))
      (node (ref "U$2") (pin "J2") (pinfunction "1_J2") (pintype "bidirectional"))
    )
    (net (code "44") (name "Net-(U$2I-1)") (class "Default")
      (node (ref "D31") (pin "A") (pinfunction "A_A") (pintype "passive"))
      (node (ref "D36") (pin "A") (pinfunction "A_A") (pintype "passive"))
      (node (ref "D42") (pin "A") (pinfunction "A_A") (pintype "passive"))
      (node (ref "D49") (pin "A") (pinfunction "A_A") (pintype "passive"))
      (node (ref "U$2") (pin "K2") (pinfunction "1_K2") (pintype "bidirectional"))
    )
    (net (code "45") (name "Net-(U$2J-1)") (class "Default")
      (node (ref "D25") (pin "A") (pinfunction "A_A") (pintype "passive"))
      (node (ref "U$2") (pin "L2") (pinfunction "1_L2") (pintype "bidirectional"))
    )
    (net (code "46") (name "Net-(U$2K-1)") (class "Default")
      (node (ref "D27") (pin "A") (pinfunction "A_A") (pintype "passive"))
      (node (ref "D30") (pin "A") (pinfunction "A_A") (pintype "passive"))
      (node (ref "D34") (pin "A") (pinfunction "A_A") (pintype "passive"))
      (node (ref "D39") (pin "A") (pinfunction "A_A") (pintype "passive"))
      (node (ref "D45") (pin "A") (pinfunction "A_A") (pintype "passive"))
      (node (ref "D52") (pin "A") (pinfunction "A_A") (pintype "passive"))
      (node (ref "U$2") (pin "M2") (pinfunction "1_M2") (pintype "bidirectional"))
    )
    (net (code "47") (name "Net-(U$2L-1)") (class "Default")
      (node (ref "R24") (pin "1") (pinfunction "1_1") (pintype "passive"))
      (node (ref "U$2") (pin "N2") (pinfunction "1_N2") (pintype "bidirectional"))
    )
    (net (code "48") (name "Net-(U$2P-1)") (class "Default")
      (node (ref "R25") (pin "2") (pinfunction "2_2") (pintype "passive"))
      (node (ref "U$2") (pin "T2") (pinfunction "1_T2") (pintype "bidirectional"))
    )
    (net (code "49") (name "Net-(U$2Q-1)") (class "Default")
      (node (ref "R23") (pin "2") (pinfunction "2_2") (pintype "passive"))
      (node (ref "U$2") (pin "U2") (pinfunction "1_U2") (pintype "bidirectional"))
    )
  )
)
